# Sheet1.net
KiCad netlist of a schematic drawn in Altium Designer
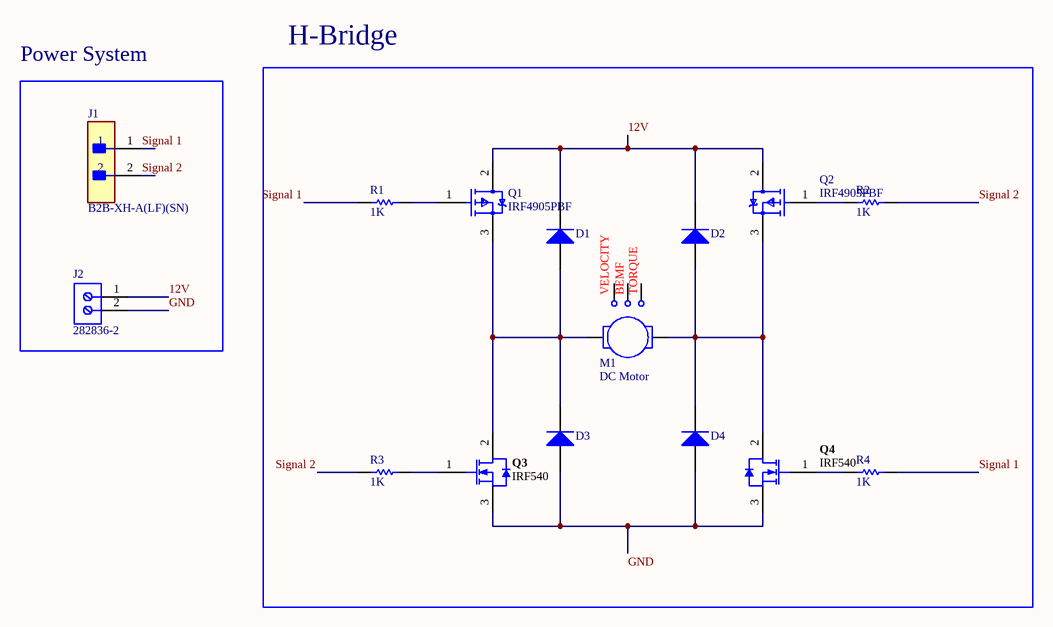
[diagram p0: Sheet1.SchDoc]

(export (version "E")
  (design (tool "Eeschema 10.0.6"))
  (components
    (comp (ref "D1") (value "Diode") (libsource (lib "Simulation Generic Components") (part "Diode")))
    (comp (ref "D2") (value "Diode") (libsource (lib "Simulation Generic Components") (part "Diode")))
    (comp (ref "D3") (value "Diode") (libsource (lib "Simulation Generic Components") (part "Diode")))
    (comp (ref "D4") (value "Diode") (libsource (lib "Simulation Generic Components") (part "Diode")))
    (comp (ref "J1")
      (value "B2B-XH-A(LF)(SN)")
      (footprint "FP-B2B-XH-A_LF_SN-MFG")
      (description "CONN HEADER VERT 2POS 2.5MM")
      (libsource (lib "Altium Content Vault") (part "3bc925449376181038e59eaffc5286c"))
    )
    (comp (ref "J2")
      (value "282836-2")
      (footprint "TECO-282836-2_V")
      (description "Female Header, Pitch 5 mm, 1 x 2 Position, Height 10 mm, Tail Length 3.5 mm, Rohs, Bulk")
      (fields (field (name "VOLTAGE") "300V") (field (name "MANUFACTURER") "TE Connectivity"))
      (libsource (lib "Altium Content Vault") (part "CN-1P-F-TB2"))
    )
    (comp (ref "M1") (value "DC Motor") (libsource (lib "Simulation Generic Components") (part "DC Motor")))
    (comp (ref "Q1")
      (value "IRF4905PBF")
      (footprint "FP-PG-TO220-3-MFG")
      (description "MOSFET P-CH 55V 74A TO-220AB")
      (libsource (lib "Altium Content Vault") (part "7c43f5ccbd0f8ca8bbf61673af0f16f"))
    )
    (comp (ref "Q2")
      (value "IRF4905PBF")
      (footprint "FP-PG-TO220-3-MFG")
      (description "MOSFET P-CH 55V 74A TO-220AB")
      (libsource (lib "Altium Content Vault") (part "7c43f5ccbd0f8ca8bbf61673af0f16f"))
    )
    (comp (ref "Q3")
      (value "IRF540")
      (footprint "VISH-TO-220AB-3_A")
      (description "Power MOSFET, 100 VDS, -55 to 175 degC, 3-Pin TO-220AB, RoHS, Tube")
      (fields (field (name "MANUFACTURER") "Vishay"))
      (libsource (lib "Altium Content Vault") (part "NEMOS-GDS-3"))
    )
    (comp (ref "Q4")
      (value "IRF540")
      (footprint "VISH-TO-220AB-3_A")
      (description "Power MOSFET, 100 VDS, -55 to 175 degC, 3-Pin TO-220AB, RoHS, Tube")
      (fields (field (name "MANUFACTURER") "Vishay"))
      (libsource (lib "Altium Content Vault") (part "NEMOS-GDS-3"))
    )
    (comp (ref "R1")
      (value "1K")
      (description "Resistor")
      (libsource (lib "Simulation Generic Components") (part "Resistor"))
    )
    (comp (ref "R2")
      (value "1K")
      (description "Resistor")
      (libsource (lib "Simulation Generic Components") (part "Resistor"))
    )
    (comp (ref "R3")
      (value "1K")
      (description "Resistor")
      (libsource (lib "Simulation Generic Components") (part "Resistor"))
    )
    (comp (ref "R4")
      (value "1K")
      (description "Resistor")
      (libsource (lib "Simulation Generic Components") (part "Resistor"))
    )
  )
  (nets
    (net (code "1") (name "/12V") (class "Default")
      (node (ref "D1") (pin "2") (pinfunction "K_2") (pintype "passive"))
      (node (ref "D2") (pin "2") (pinfunction "K_2") (pintype "passive"))
      (node (ref "J2") (pin "1") (pinfunction "1_1") (pintype "passive"))
      (node (ref "Q1") (pin "2") (pinfunction "DRAIN_2") (pintype "passive"))
      (node (ref "Q2") (pin "2") (pinfunction "DRAIN_2") (pintype "passive"))
    )
    (net (code "2") (name "/GND") (class "Default")
      (node (ref "D3") (pin "1") (pinfunction "A_1") (pintype "passive"))
      (node (ref "D4") (pin "1") (pinfunction "A_1") (pintype "passive"))
      (node (ref "J2") (pin "2") (pinfunction "2_2") (pintype "passive"))
      (node (ref "Q3") (pin "3") (pinfunction "S_3") (pintype "passive"))
      (node (ref "Q4") (pin "3") (pinfunction "S_3") (pintype "passive"))
    )
    (net (code "3") (name "/Signal 1") (class "Default")
      (node (ref "J1") (pin "1") (pinfunction "1_1") (pintype "passive"))
      (node (ref "R1") (pin "1") (pinfunction "1_1") (pintype "passive"))
      (node (ref "R4") (pin "2") (pinfunction "2_2") (pintype "passive"))
    )
    (net (code "4") (name "/Signal 2") (class "Default")
      (node (ref "J1") (pin "2") (pinfunction "2_2") (pintype "passive"))
      (node (ref "R2") (pin "2") (pinfunction "2_2") (pintype "passive"))
      (node (ref "R3") (pin "1") (pinfunction "1_1") (pintype "passive"))
    )
    (net (code "5") (name "Net-(D1-A)") (class "Default")
      (node (ref "D1") (pin "1") (pinfunction "A_1") (pintype "passive"))
      (node (ref "D3") (pin "2") (pinfunction "K_2") (pintype "passive"))
      (node (ref "M1") (pin "1") (pinfunction "1_1") (pintype "passive"))
      (node (ref "Q1") (pin "3") (pinfunction "SOURCE_3") (pintype "passive"))
      (node (ref "Q3") (pin "2") (pinfunction "D_2") (pintype "passive"))
    )
    (net (code "6") (name "Net-(D2-A)") (class "Default")
      (node (ref "D2") (pin "1") (pinfunction "A_1") (pintype "passive"))
      (node (ref "D4") (pin "2") (pinfunction "K_2") (pintype "passive"))
      (node (ref "M1") (pin "2") (pinfunction "2_2") (pintype "passive"))
      (node (ref "Q2") (pin "3") (pinfunction "SOURCE_3") (pintype "passive"))
      (node (ref "Q4") (pin "2") (pinfunction "D_2") (pintype "passive"))
    )
    (net (code "7") (name "Net-(Q1-GATE)") (class "Default")
      (node (ref "Q1") (pin "1") (pinfunction "GATE_1") (pintype "passive"))
      (node (ref "R1") (pin "2") (pinfunction "2_2") (pintype "passive"))
    )
    (net (code "8") (name "Net-(Q2-GATE)") (class "Default")
      (node (ref "Q2") (pin "1") (pinfunction "GATE_1") (pintype "passive"))
      (node (ref "R2") (pin "1") (pinfunction "1_1") (pintype "passive"))
    )
    (net (code "9") (name "Net-(Q3-G)") (class "Default")
      (node (ref "Q3") (pin "1") (pinfunction "G_1") (pintype "passive"))
      (node (ref "R3") (pin "2") (pinfunction "2_2") (pintype "passive"))
    )
    (net (code "10") (name "Net-(Q4-G)") (class "Default")
      (node (ref "Q4") (pin "1") (pinfunction "G_1") (pintype "passive"))
      (node (ref "R4") (pin "1") (pinfunction "1_1") (pintype "passive"))
    )
    (net (code "11") (name "unconnected-(M1-Pad3)") (class "Default")
      (node (ref "M1") (pin "3") (pinfunction "3_3") (pintype "passive"))
    )
    (net (code "12") (name "unconnected-(M1-Pad4)") (class "Default")
      (node (ref "M1") (pin "4") (pinfunction "4_4") (pintype "passive"))
    )
    (net (code "13") (name "unconnected-(M1-Pad5)") (class "Default")
      (node (ref "M1") (pin "5") (pinfunction "5_5") (pintype "passive"))
    )
  )
)
